# ZXseries.net
KiCad netlist of a schematic drawn in EAGLE
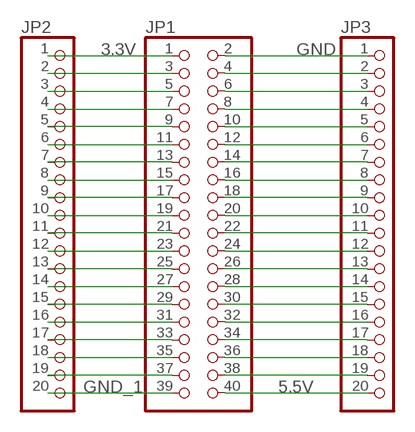
[diagram p0: schematic, sheet 1]

(export (version "E")
  (design (tool "Eeschema 10.0.6"))
  (components
    (comp (ref "JP1")
      (value "PINHD-2X20")
      (footprint "eagle-import:2X20")
      (libsource (lib "eagle-import") (part "PINHD-2X20"))
    )
    (comp (ref "JP2")
      (value "PINHD-1X20")
      (footprint "eagle-import:1X20")
      (libsource (lib "eagle-import") (part "PINHD-1X20"))
    )
    (comp (ref "JP3")
      (value "PINHD-1X20")
      (footprint "eagle-import:1X20")
      (libsource (lib "eagle-import") (part "PINHD-1X20"))
    )
  )
  (nets
    (net (code "1") (name "/3.3V") (class "Default")
      (node (ref "JP1") (pin "1") (pinfunction "1_1") (pintype "passive"))
      (node (ref "JP2") (pin "1") (pinfunction "1_1") (pintype "passive"))
    )
    (net (code "2") (name "/5.5V") (class "Default")
      (node (ref "JP1") (pin "40") (pinfunction "40_40") (pintype "passive"))
      (node (ref "JP3") (pin "20") (pinfunction "20_20") (pintype "passive"))
    )
    (net (code "3") (name "/GND") (class "Default")
      (node (ref "JP1") (pin "2") (pinfunction "2_2") (pintype "passive"))
      (node (ref "JP3") (pin "1") (pinfunction "1_1") (pintype "passive"))
    )
    (net (code "4") (name "/GND_1") (class "Default")
      (node (ref "JP1") (pin "39") (pinfunction "39_39") (pintype "passive"))
      (node (ref "JP2") (pin "20") (pinfunction "20_20") (pintype "passive"))
    )
    (net (code "5") (name "Net-(JP1-Pad3)") (class "Default")
      (node (ref "JP1") (pin "3") (pinfunction "3_3") (pintype "passive"))
      (node (ref "JP2") (pin "2") (pinfunction "2_2") (pintype "passive"))
    )
    (net (code "6") (name "Net-(JP1-Pad4)") (class "Default")
      (node (ref "JP1") (pin "4") (pinfunction "4_4") (pintype "passive"))
      (node (ref "JP3") (pin "2") (pinfunction "2_2") (pintype "passive"))
    )
    (net (code "7") (name "Net-(JP1-Pad5)") (class "Default")
      (node (ref "JP1") (pin "5") (pinfunction "5_5") (pintype "passive"))
      (node (ref "JP2") (pin "3") (pinfunction "3_3") (pintype "passive"))
    )
    (net (code "8") (name "Net-(JP1-Pad6)") (class "Default")
      (node (ref "JP1") (pin "6") (pinfunction "6_6") (pintype "passive"))
      (node (ref "JP3") (pin "3") (pinfunction "3_3") (pintype "passive"))
    )
    (net (code "9") (name "Net-(JP1-Pad7)") (class "Default")
      (node (ref "JP1") (pin "7") (pinfunction "7_7") (pintype "passive"))
      (node (ref "JP2") (pin "4") (pinfunction "4_4") (pintype "passive"))
    )
    (net (code "10") (name "Net-(JP1-Pad8)") (class "Default")
      (node (ref "JP1") (pin "8") (pinfunction "8_8") (pintype "passive"))
      (node (ref "JP3") (pin "4") (pinfunction "4_4") (pintype "passive"))
    )
    (net (code "11") (name "Net-(JP1-Pad9)") (class "Default")
      (node (ref "JP1") (pin "9") (pinfunction "9_9") (pintype "passive"))
      (node (ref "JP2") (pin "5") (pinfunction "5_5") (pintype "passive"))
    )
    (net (code "12") (name "Net-(JP1-Pad10)") (class "Default")
      (node (ref "JP1") (pin "10") (pinfunction "10_10") (pintype "passive"))
      (node (ref "JP3") (pin "5") (pinfunction "5_5") (pintype "passive"))
    )
    (net (code "13") (name "Net-(JP1-Pad11)") (class "Default")
      (node (ref "JP1") (pin "11") (pinfunction "11_11") (pintype "passive"))
      (node (ref "JP2") (pin "6") (pinfunction "6_6") (pintype "passive"))
    )
    (net (code "14") (name "Net-(JP1-Pad12)") (class "Default")
      (node (ref "JP1") (pin "12") (pinfunction "12_12") (pintype "passive"))
      (node (ref "JP3") (pin "6") (pinfunction "6_6") (pintype "passive"))
    )
    (net (code "15") (name "Net-(JP1-Pad13)") (class "Default")
      (node (ref "JP1") (pin "13") (pinfunction "13_13") (pintype "passive"))
      (node (ref "JP2") (pin "7") (pinfunction "7_7") (pintype "passive"))
    )
    (net (code "16") (name "Net-(JP1-Pad14)") (class "Default")
      (node (ref "JP1") (pin "14") (pinfunction "14_14") (pintype "passive"))
      (node (ref "JP3") (pin "7") (pinfunction "7_7") (pintype "passive"))
    )
    (net (code "17") (name "Net-(JP1-Pad15)") (class "Default")
      (node (ref "JP1") (pin "15") (pinfunction "15_15") (pintype "passive"))
      (node (ref "JP2") (pin "8") (pinfunction "8_8") (pintype "passive"))
    )
    (net (code "18") (name "Net-(JP1-Pad16)") (class "Default")
      (node (ref "JP1") (pin "16") (pinfunction "16_16") (pintype "passive"))
      (node (ref "JP3") (pin "8") (pinfunction "8_8") (pintype "passive"))
    )
    (net (code "19") (name "Net-(JP1-Pad17)") (class "Default")
      (node (ref "JP1") (pin "17") (pinfunction "17_17") (pintype "passive"))
      (node (ref "JP2") (pin "9") (pinfunction "9_9") (pintype "passive"))
    )
    (net (code "20") (name "Net-(JP1-Pad18)") (class "Default")
      (node (ref "JP1") (pin "18") (pinfunction "18_18") (pintype "passive"))
      (node (ref "JP3") (pin "9") (pinfunction "9_9") (pintype "passive"))
    )
    (net (code "21") (name "Net-(JP1-Pad19)") (class "Default")
      (node (ref "JP1") (pin "19") (pinfunction "19_19") (pintype "passive"))
      (node (ref "JP2") (pin "10") (pinfunction "10_10") (pintype "passive"))
    )
    (net (code "22") (name "Net-(JP1-Pad20)") (class "Default")
      (node (ref "JP1") (pin "20") (pinfunction "20_20") (pintype "passive"))
      (node (ref "JP3") (pin "10") (pinfunction "10_10") (pintype "passive"))
    )
    (net (code "23") (name "Net-(JP1-Pad21)") (class "Default")
      (node (ref "JP1") (pin "21") (pinfunction "21_21") (pintype "passive"))
      (node (ref "JP2") (pin "11") (pinfunction "11_11") (pintype "passive"))
    )
    (net (code "24") (name "Net-(JP1-Pad22)") (class "Default")
      (node (ref "JP1") (pin "22") (pinfunction "22_22") (pintype "passive"))
      (node (ref "JP3") (pin "11") (pinfunction "11_11") (pintype "passive"))
    )
    (net (code "25") (name "Net-(JP1-Pad23)") (class "Default")
      (node (ref "JP1") (pin "23") (pinfunction "23_23") (pintype "passive"))
      (node (ref "JP2") (pin "12") (pinfunction "12_12") (pintype "passive"))
    )
    (net (code "26") (name "Net-(JP1-Pad24)") (class "Default")
      (node (ref "JP1") (pin "24") (pinfunction "24_24") (pintype "passive"))
      (node (ref "JP3") (pin "12") (pinfunction "12_12") (pintype "passive"))
    )
    (net (code "27") (name "Net-(JP1-Pad25)") (class "Default")
      (node (ref "JP1") (pin "25") (pinfunction "25_25") (pintype "passive"))
      (node (ref "JP2") (pin "13") (pinfunction "13_13") (pintype "passive"))
    )
    (net (code "28") (name "Net-(JP1-Pad26)") (class "Default")
      (node (ref "JP1") (pin "26") (pinfunction "26_26") (pintype "passive"))
      (node (ref "JP3") (pin "13") (pinfunction "13_13") (pintype "passive"))
    )
    (net (code "29") (name "Net-(JP1-Pad27)") (class "Default")
      (node (ref "JP1") (pin "27") (pinfunction "27_27") (pintype "passive"))
      (node (ref "JP2") (pin "14") (pinfunction "14_14") (pintype "passive"))
    )
    (net (code "30") (name "Net-(JP1-Pad28)") (class "Default")
      (node (ref "JP1") (pin "28") (pinfunction "28_28") (pintype "passive"))
      (node (ref "JP3") (pin "14") (pinfunction "14_14") (pintype "passive"))
    )
    (net (code "31") (name "Net-(JP1-Pad29)") (class "Default")
      (node (ref "JP1") (pin "29") (pinfunction "29_29") (pintype "passive"))
      (node (ref "JP2") (pin "15") (pinfunction "15_15") (pintype "passive"))
    )
    (net (code "32") (name "Net-(JP1-Pad30)") (class "Default")
      (node (ref "JP1") (pin "30") (pinfunction "30_30") (pintype "passive"))
      (node (ref "JP3") (pin "15") (pinfunction "15_15") (pintype "passive"))
    )
    (net (code "33") (name "Net-(JP1-Pad31)") (class "Default")
      (node (ref "JP1") (pin "31") (pinfunction "31_31") (pintype "passive"))
      (node (ref "JP2") (pin "16") (pinfunction "16_16") (pintype "passive"))
    )
    (net (code "34") (name "Net-(JP1-Pad32)") (class "Default")
      (node (ref "JP1") (pin "32") (pinfunction "32_32") (pintype "passive"))
      (node (ref "JP3") (pin "16") (pinfunction "16_16") (pintype "passive"))
    )
    (net (code "35") (name "Net-(JP1-Pad33)") (class "Default")
      (node (ref "JP1") (pin "33") (pinfunction "33_33") (pintype "passive"))
      (node (ref "JP2") (pin "17") (pinfunction "17_17") (pintype "passive"))
    )
    (net (code "36") (name "Net-(JP1-Pad34)") (class "Default")
      (node (ref "JP1") (pin "34") (pinfunction "34_34") (pintype "passive"))
      (node (ref "JP3") (pin "17") (pinfunction "17_17") (pintype "passive"))
    )
    (net (code "37") (name "Net-(JP1-Pad35)") (class "Default")
      (node (ref "JP1") (pin "35") (pinfunction "35_35") (pintype "passive"))
      (node (ref "JP2") (pin "18") (pinfunction "18_18") (pintype "passive"))
    )
    (net (code "38") (name "Net-(JP1-Pad36)") (class "Default")
      (node (ref "JP1") (pin "36") (pinfunction "36_36") (pintype "passive"))
      (node (ref "JP3") (pin "18") (pinfunction "18_18") (pintype "passive"))
    )
    (net (code "39") (name "Net-(JP1-Pad37)") (class "Default")
      (node (ref "JP1") (pin "37") (pinfunction "37_37") (pintype "passive"))
      (node (ref "JP2") (pin "19") (pinfunction "19_19") (pintype "passive"))
    )
    (net (code "40") (name "Net-(JP1-Pad38)") (class "Default")
      (node (ref "JP1") (pin "38") (pinfunction "38_38") (pintype "passive"))
      (node (ref "JP3") (pin "19") (pinfunction "19_19") (pintype "passive"))
    )
  )
)
